# MT9V034.net
KiCad netlist of a schematic drawn in Altium Designer
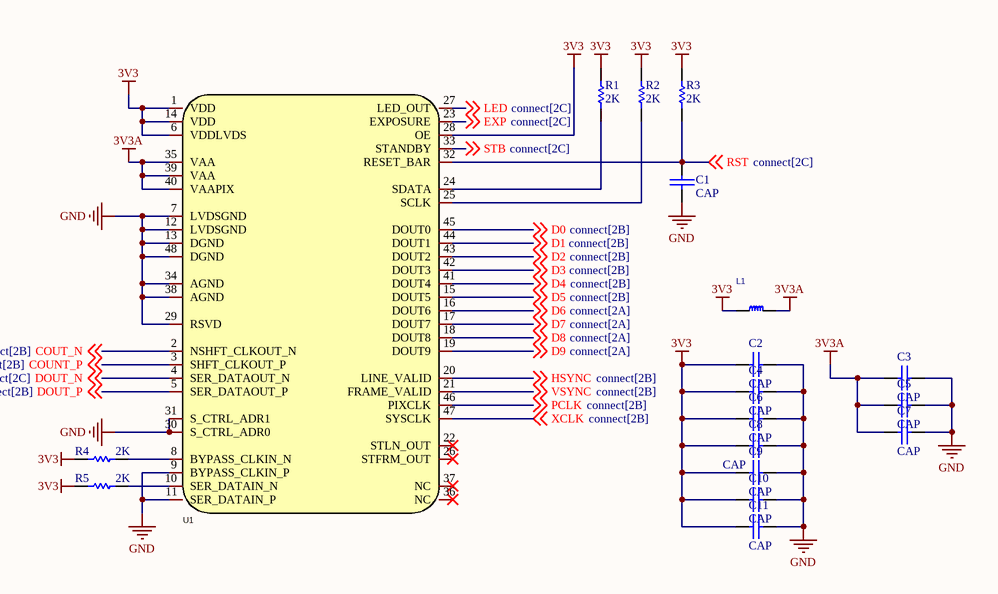
[diagram p0: MT9V034.SchDoc]

(export (version "E")
  (design (tool "Eeschema 10.0.6"))
  (components
    (comp (ref "C1")
      (value "CAP")
      (footprint "C0603")
      (description "无极性电容")
      (libsource (lib "01-02.电容") (part "CAP"))
    )
    (comp (ref "C2")
      (value "CAP")
      (footprint "C0603")
      (description "无极性电容")
      (libsource (lib "01-02.电容") (part "CAP"))
    )
    (comp (ref "C3")
      (value "CAP")
      (footprint "C0603")
      (description "无极性电容")
      (libsource (lib "01-02.电容") (part "CAP"))
    )
    (comp (ref "C4")
      (value "CAP")
      (footprint "C0603")
      (description "无极性电容")
      (libsource (lib "01-02.电容") (part "CAP"))
    )
    (comp (ref "C5")
      (value "CAP")
      (footprint "C0603")
      (description "无极性电容")
      (libsource (lib "01-02.电容") (part "CAP"))
    )
    (comp (ref "C6")
      (value "CAP")
      (footprint "C0603")
      (description "无极性电容")
      (libsource (lib "01-02.电容") (part "CAP"))
    )
    (comp (ref "C7")
      (value "CAP")
      (footprint "C0603")
      (description "无极性电容")
      (libsource (lib "01-02.电容") (part "CAP"))
    )
    (comp (ref "C8")
      (value "CAP")
      (footprint "C0603")
      (description "无极性电容")
      (libsource (lib "01-02.电容") (part "CAP"))
    )
    (comp (ref "C9")
      (value "CAP")
      (footprint "C0603")
      (description "无极性电容")
      (libsource (lib "01-02.电容") (part "CAP"))
    )
    (comp (ref "C10")
      (value "CAP")
      (footprint "C0603")
      (description "无极性电容")
      (libsource (lib "01-02.电容") (part "CAP"))
    )
    (comp (ref "C11")
      (value "CAP")
      (footprint "C0603")
      (description "无极性电容")
      (libsource (lib "01-02.电容") (part "CAP"))
    )
    (comp (ref "L1")
      (value "FB")
      (footprint "L0603")
      (description "铁氧体磁珠")
      (libsource (lib "01-03.电感") (part "FB"))
    )
    (comp (ref "R1")
      (value "2K")
      (footprint "R0603")
      (description "电阻")
      (libsource (lib "01-01.电阻") (part "RES"))
    )
    (comp (ref "R2")
      (value "2K")
      (footprint "R0603")
      (description "电阻")
      (libsource (lib "01-01.电阻") (part "RES"))
    )
    (comp (ref "R3")
      (value "2K")
      (footprint "R0603")
      (description "电阻")
      (libsource (lib "01-01.电阻") (part "RES"))
    )
    (comp (ref "R4")
      (value "2K")
      (footprint "R0603")
      (description "电阻")
      (libsource (lib "01-01.电阻") (part "RES"))
    )
    (comp (ref "R5")
      (value "2K")
      (footprint "R0603")
      (description "电阻")
      (libsource (lib "01-01.电阻") (part "RES"))
    )
    (comp (ref "U1")
      (value "MT9V034C12STM-DP")
      (footprint "CLCC-48_L11.4-W11.4-P0.80-T")
      (fields (field (name "MANUFACTURER") "onsemi(安森美)"))
      (libsource (lib "04-01.传感器") (part "MT9V034C12STM-DP"))
    )
  )
  (nets
    (net (code "1") (name "3V3") (class "Default")
      (node (ref "C10") (pin "1") (pinfunction "1_1") (pintype "passive"))
      (node (ref "C11") (pin "1") (pinfunction "1_1") (pintype "passive"))
      (node (ref "C2") (pin "1") (pinfunction "1_1") (pintype "passive"))
      (node (ref "C4") (pin "1") (pinfunction "1_1") (pintype "passive"))
      (node (ref "C6") (pin "1") (pinfunction "1_1") (pintype "passive"))
      (node (ref "C8") (pin "1") (pinfunction "1_1") (pintype "passive"))
      (node (ref "C9") (pin "1") (pinfunction "1_1") (pintype "passive"))
      (node (ref "L1") (pin "1") (pinfunction "1_1") (pintype "passive"))
      (node (ref "R1") (pin "2") (pinfunction "2_2") (pintype "passive"))
      (node (ref "R2") (pin "2") (pinfunction "2_2") (pintype "passive"))
      (node (ref "R3") (pin "2") (pinfunction "2_2") (pintype "passive"))
      (node (ref "R4") (pin "1") (pinfunction "1_1") (pintype "passive"))
      (node (ref "R5") (pin "1") (pinfunction "1_1") (pintype "passive"))
      (node (ref "U1") (pin "1") (pinfunction "VDD_1") (pintype "passive"))
      (node (ref "U1") (pin "14") (pinfunction "VDD_14") (pintype "passive"))
      (node (ref "U1") (pin "28") (pinfunction "OE_28") (pintype "passive"))
      (node (ref "U1") (pin "6") (pinfunction "VDDLVDS_6") (pintype "passive"))
    )
    (net (code "2") (name "3V3A") (class "Default")
      (node (ref "C3") (pin "1") (pinfunction "1_1") (pintype "passive"))
      (node (ref "C5") (pin "1") (pinfunction "1_1") (pintype "passive"))
      (node (ref "C7") (pin "1") (pinfunction "1_1") (pintype "passive"))
      (node (ref "L1") (pin "2") (pinfunction "2_2") (pintype "passive"))
      (node (ref "U1") (pin "35") (pinfunction "VAA_35") (pintype "passive"))
      (node (ref "U1") (pin "39") (pinfunction "VAA_39") (pintype "passive"))
      (node (ref "U1") (pin "40") (pinfunction "VAAPIX_40") (pintype "passive"))
    )
    (net (code "3") (name "COUNT_P") (class "Default")
      (node (ref "U1") (pin "3") (pinfunction "SHFT_CLKOUT_P_3") (pintype "passive"))
    )
    (net (code "4") (name "COUT_N") (class "Default")
      (node (ref "U1") (pin "2") (pinfunction "NSHFT_CLKOUT_N_2") (pintype "passive"))
    )
    (net (code "5") (name "D0") (class "Default")
      (node (ref "U1") (pin "45") (pinfunction "DOUT0_45") (pintype "passive"))
    )
    (net (code "6") (name "D1") (class "Default")
      (node (ref "U1") (pin "44") (pinfunction "DOUT1_44") (pintype "passive"))
    )
    (net (code "7") (name "D2") (class "Default")
      (node (ref "U1") (pin "43") (pinfunction "DOUT2_43") (pintype "passive"))
    )
    (net (code "8") (name "D3") (class "Default")
      (node (ref "U1") (pin "42") (pinfunction "DOUT3_42") (pintype "passive"))
    )
    (net (code "9") (name "D4") (class "Default")
      (node (ref "U1") (pin "41") (pinfunction "DOUT4_41") (pintype "passive"))
    )
    (net (code "10") (name "D5") (class "Default")
      (node (ref "U1") (pin "15") (pinfunction "DOUT5_15") (pintype "passive"))
    )
    (net (code "11") (name "D6") (class "Default")
      (node (ref "U1") (pin "16") (pinfunction "DOUT6_16") (pintype "passive"))
    )
    (net (code "12") (name "D7") (class "Default")
      (node (ref "U1") (pin "17") (pinfunction "DOUT7_17") (pintype "passive"))
    )
    (net (code "13") (name "D8") (class "Default")
      (node (ref "U1") (pin "18") (pinfunction "DOUT8_18") (pintype "passive"))
    )
    (net (code "14") (name "D9") (class "Default")
      (node (ref "U1") (pin "19") (pinfunction "DOUT9_19") (pintype "passive"))
    )
    (net (code "15") (name "DOUT_N") (class "Default")
      (node (ref "U1") (pin "4") (pinfunction "SER_DATAOUT_N_4") (pintype "passive"))
    )
    (net (code "16") (name "DOUT_P") (class "Default")
      (node (ref "U1") (pin "5") (pinfunction "SER_DATAOUT_P_5") (pintype "passive"))
    )
    (net (code "17") (name "EXP") (class "Default")
      (node (ref "U1") (pin "23") (pinfunction "EXPOSURE_23") (pintype "passive"))
    )
    (net (code "18") (name "GND") (class "Default")
      (node (ref "C1") (pin "1") (pinfunction "1_1") (pintype "passive"))
      (node (ref "C10") (pin "2") (pinfunction "2_2") (pintype "passive"))
      (node (ref "C11") (pin "2") (pinfunction "2_2") (pintype "passive"))
      (node (ref "C2") (pin "2") (pinfunction "2_2") (pintype "passive"))
      (node (ref "C3") (pin "2") (pinfunction "2_2") (pintype "passive"))
      (node (ref "C4") (pin "2") (pinfunction "2_2") (pintype "passive"))
      (node (ref "C5") (pin "2") (pinfunction "2_2") (pintype "passive"))
      (node (ref "C6") (pin "2") (pinfunction "2_2") (pintype "passive"))
      (node (ref "C7") (pin "2") (pinfunction "2_2") (pintype "passive"))
      (node (ref "C8") (pin "2") (pinfunction "2_2") (pintype "passive"))
      (node (ref "C9") (pin "2") (pinfunction "2_2") (pintype "passive"))
      (node (ref "U1") (pin "11") (pinfunction "SER_DATAIN_P_11") (pintype "passive"))
      (node (ref "U1") (pin "12") (pinfunction "LVDSGND_12") (pintype "passive"))
      (node (ref "U1") (pin "13") (pinfunction "DGND_13") (pintype "passive"))
      (node (ref "U1") (pin "29") (pinfunction "RSVD_29") (pintype "passive"))
      (node (ref "U1") (pin "30") (pinfunction "S_CTRL_ADR0_30") (pintype "passive"))
      (node (ref "U1") (pin "31") (pinfunction "S_CTRL_ADR1_31") (pintype "passive"))
      (node (ref "U1") (pin "34") (pinfunction "AGND_34") (pintype "passive"))
      (node (ref "U1") (pin "38") (pinfunction "AGND_38") (pintype "passive"))
      (node (ref "U1") (pin "48") (pinfunction "DGND_48") (pintype "passive"))
      (node (ref "U1") (pin "7") (pinfunction "LVDSGND_7") (pintype "passive"))
      (node (ref "U1") (pin "9") (pinfunction "BYPASS_CLKIN_P_9") (pintype "passive"))
    )
    (net (code "19") (name "HSYNC") (class "Default")
      (node (ref "U1") (pin "20") (pinfunction "LINE_VALID_20") (pintype "passive"))
    )
    (net (code "20") (name "LED") (class "Default")
      (node (ref "U1") (pin "27") (pinfunction "LED_OUT_27") (pintype "passive"))
    )
    (net (code "21") (name "Net-(U1-BYPASS_CLKIN_N)") (class "Default")
      (node (ref "R4") (pin "2") (pinfunction "2_2") (pintype "passive"))
      (node (ref "U1") (pin "8") (pinfunction "BYPASS_CLKIN_N_8") (pintype "passive"))
    )
    (net (code "22") (name "Net-(U1-SCLK)") (class "Default")
      (node (ref "R2") (pin "1") (pinfunction "1_1") (pintype "passive"))
      (node (ref "U1") (pin "25") (pinfunction "SCLK_25") (pintype "passive"))
    )
    (net (code "23") (name "Net-(U1-SDATA)") (class "Default")
      (node (ref "R1") (pin "1") (pinfunction "1_1") (pintype "passive"))
      (node (ref "U1") (pin "24") (pinfunction "SDATA_24") (pintype "passive"))
    )
    (net (code "24") (name "Net-(U1-SER_DATAIN_N)") (class "Default")
      (node (ref "R5") (pin "2") (pinfunction "2_2") (pintype "passive"))
      (node (ref "U1") (pin "10") (pinfunction "SER_DATAIN_N_10") (pintype "passive"))
    )
    (net (code "25") (name "PCLK") (class "Default")
      (node (ref "U1") (pin "46") (pinfunction "PIXCLK_46") (pintype "passive"))
    )
    (net (code "26") (name "RST") (class "Default")
      (node (ref "C1") (pin "2") (pinfunction "2_2") (pintype "passive"))
      (node (ref "R3") (pin "1") (pinfunction "1_1") (pintype "passive"))
      (node (ref "U1") (pin "32") (pinfunction "RESET_BAR_32") (pintype "passive"))
    )
    (net (code "27") (name "STB") (class "Default")
      (node (ref "U1") (pin "33") (pinfunction "STANDBY_33") (pintype "passive"))
    )
    (net (code "28") (name "VSYNC") (class "Default")
      (node (ref "U1") (pin "21") (pinfunction "FRAME_VALID_21") (pintype "passive"))
    )
    (net (code "29") (name "XCLK") (class "Default")
      (node (ref "U1") (pin "47") (pinfunction "SYSCLK_47") (pintype "passive"))
    )
    (net (code "30") (name "unconnected-(U1-NC-Pad36)") (class "Default")
      (node (ref "U1") (pin "36") (pinfunction "NC_36") (pintype "passive+no_connect"))
    )
    (net (code "31") (name "unconnected-(U1-NC-Pad37)") (class "Default")
      (node (ref "U1") (pin "37") (pinfunction "NC_37") (pintype "passive+no_connect"))
    )
    (net (code "32") (name "unconnected-(U1-STFRM_OUT-Pad26)") (class "Default")
      (node (ref "U1") (pin "26") (pinfunction "STFRM_OUT_26") (pintype "passive+no_connect"))
    )
    (net (code "33") (name "unconnected-(U1-STLN_OUT-Pad22)") (class "Default")
      (node (ref "U1") (pin "22") (pinfunction "STLN_OUT_22") (pintype "passive+no_connect"))
    )
  )
)
